# GUC_KATMANI.net
KiCad netlist of a schematic drawn in EAGLE
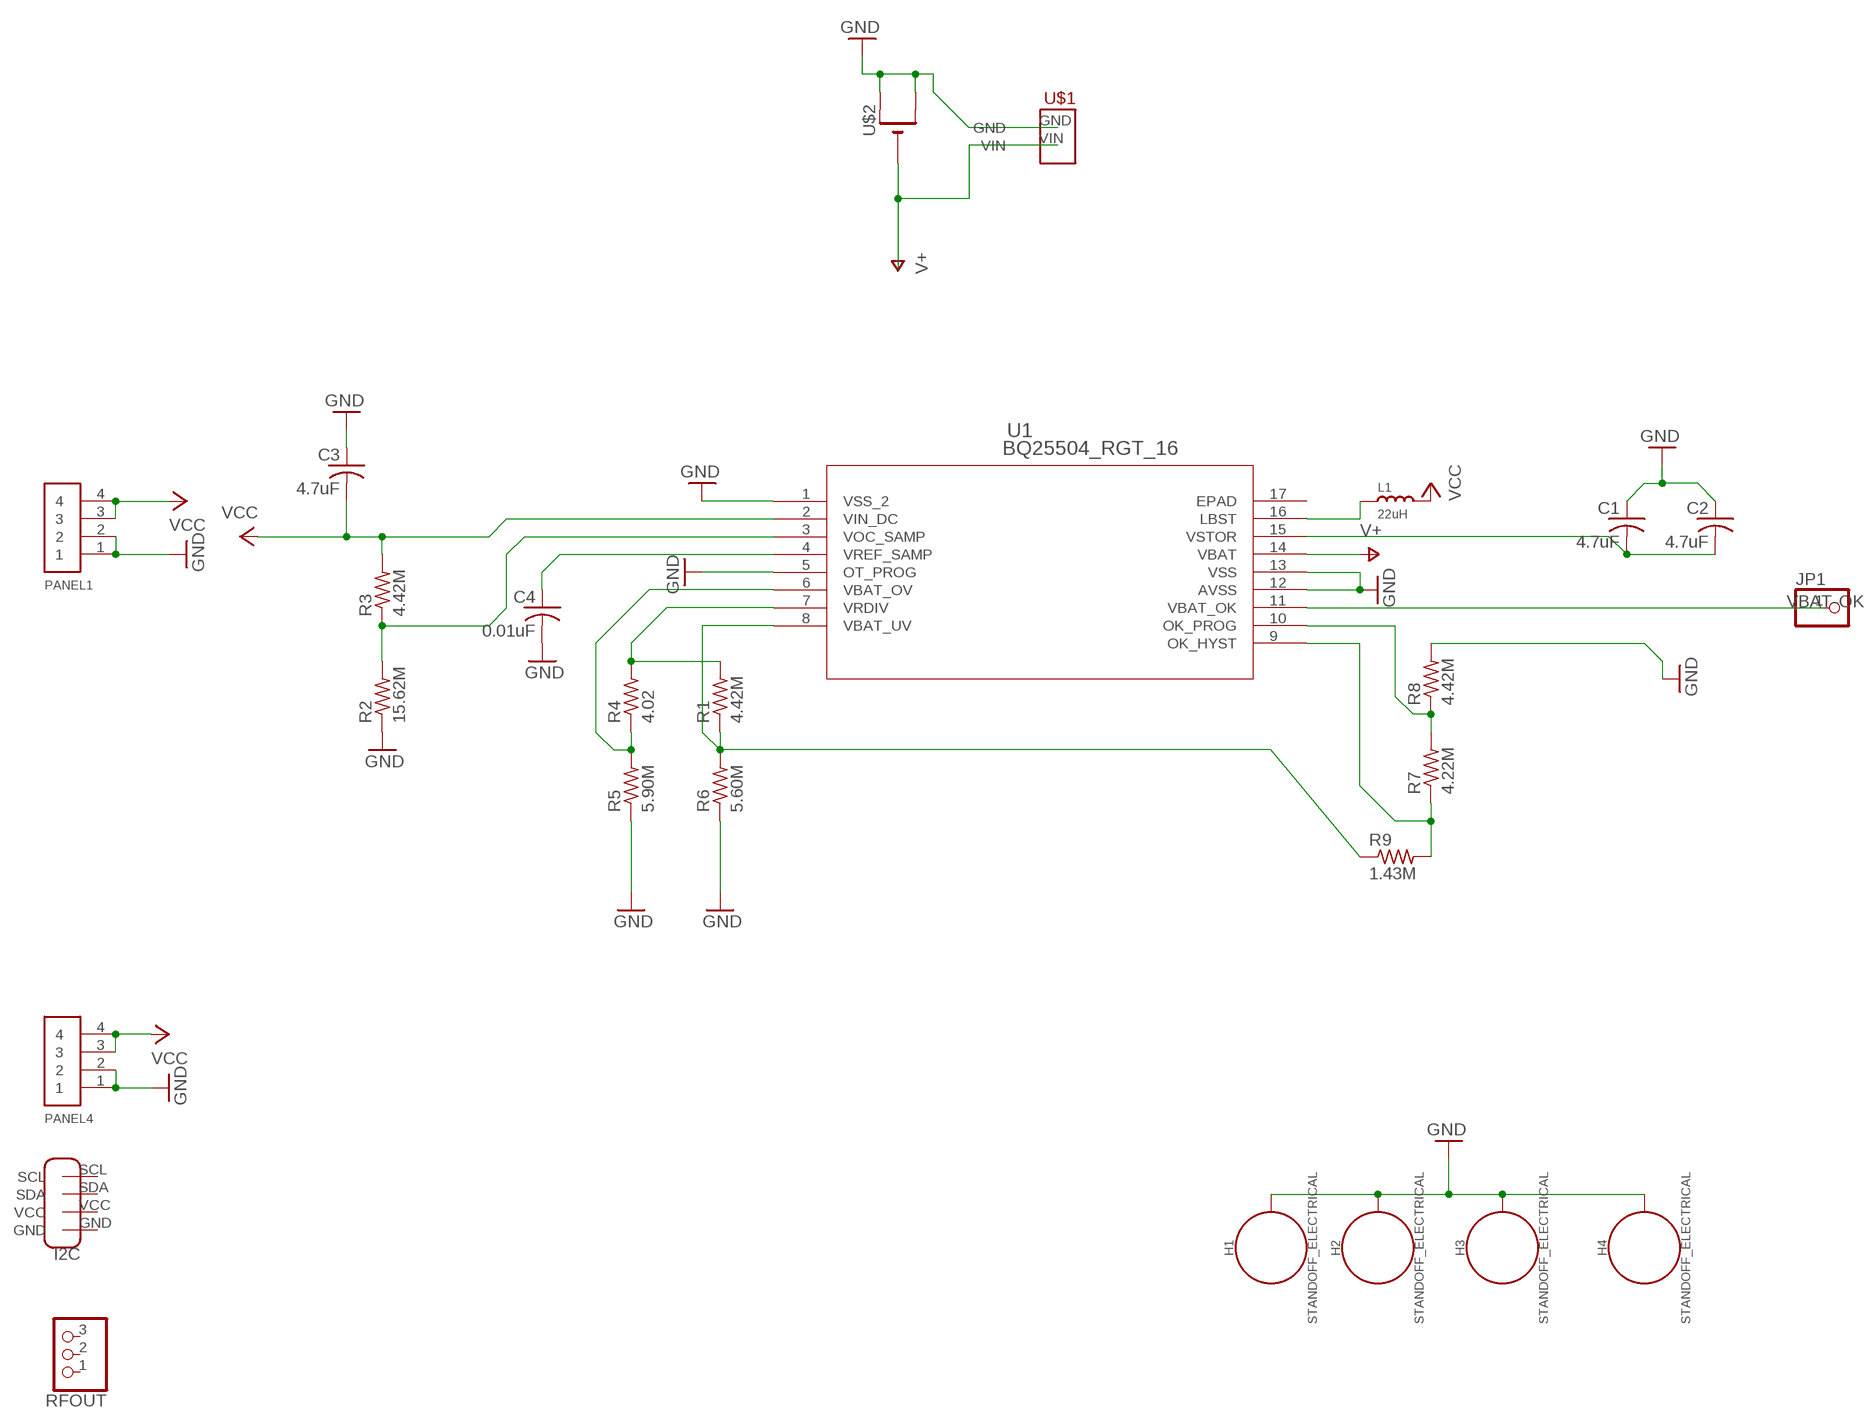
[diagram p0: schematic, sheet 1]

(export (version "E")
  (design (tool "Eeschema 10.0.6"))
  (components
    (comp (ref "C1")
      (value "4.7uF")
      (footprint "eagle-import:C0805K")
      (libsource (lib "eagle-import") (part "C-USC0805K"))
    )
    (comp (ref "C2")
      (value "4.7uF")
      (footprint "eagle-import:C0805K")
      (libsource (lib "eagle-import") (part "C-USC0805K"))
    )
    (comp (ref "C3")
      (value "4.7uF")
      (footprint "eagle-import:C0805K")
      (libsource (lib "eagle-import") (part "C-USC0805K"))
    )
    (comp (ref "C4")
      (value "0.01uF")
      (footprint "eagle-import:C0805K")
      (libsource (lib "eagle-import") (part "C-USC0805K"))
    )
    (comp (ref "H1")
      (value "STANDOFF_ELECTRICAL")
      (footprint "eagle-import:STANDOFF-ELECTRICAL")
      (libsource (lib "eagle-import") (part "STANDOFF_ELECTRICAL"))
    )
    (comp (ref "H2")
      (value "STANDOFF_ELECTRICAL")
      (footprint "eagle-import:STANDOFF-ELECTRICAL")
      (libsource (lib "eagle-import") (part "STANDOFF_ELECTRICAL"))
    )
    (comp (ref "H3")
      (value "STANDOFF_ELECTRICAL")
      (footprint "eagle-import:STANDOFF-ELECTRICAL")
      (libsource (lib "eagle-import") (part "STANDOFF_ELECTRICAL"))
    )
    (comp (ref "H4")
      (value "STANDOFF_ELECTRICAL")
      (footprint "eagle-import:STANDOFF-ELECTRICAL")
      (libsource (lib "eagle-import") (part "STANDOFF_ELECTRICAL"))
    )
    (comp (ref "JP1")
      (value "PINHD-1X1CB")
      (footprint "eagle-import:1X01-CLEANBIG")
      (libsource (lib "eagle-import") (part "PINHD-1X1CB"))
    )
    (comp (ref "L1")
      (value "22uH")
      (footprint "eagle-import:L0805")
      (fields (field (name "MPN") "BLM21PG331SN1D"))
      (libsource (lib "eagle-import") (part "SMD-FERRITE-BEAD-330R-1500MA(0805)'0805'"))
    )
    (comp (ref "PANEL1")
      (value "1X4-CLEANBIG")
      (footprint "eagle-import:1X04-CLEANBIG")
      (libsource (lib "eagle-import") (part "1X4-CLEANBIG"))
    )
    (comp (ref "PANEL4")
      (value "1X4-CLEANBIG")
      (footprint "eagle-import:1X04-CLEANBIG")
      (libsource (lib "eagle-import") (part "1X4-CLEANBIG"))
    )
    (comp (ref "R1")
      (value "4.42M")
      (footprint "eagle-import:R0805")
      (libsource (lib "eagle-import") (part "R-US_R0805"))
    )
    (comp (ref "R2")
      (value "15.62M")
      (footprint "eagle-import:R0805")
      (libsource (lib "eagle-import") (part "R-US_R0805"))
    )
    (comp (ref "R3")
      (value "4.42M")
      (footprint "eagle-import:R0805")
      (libsource (lib "eagle-import") (part "R-US_R0805"))
    )
    (comp (ref "R4")
      (value "4.02")
      (footprint "eagle-import:R0805")
      (libsource (lib "eagle-import") (part "R-US_R0805"))
    )
    (comp (ref "R5")
      (value "5.90M")
      (footprint "eagle-import:R0805")
      (libsource (lib "eagle-import") (part "R-US_R0805"))
    )
    (comp (ref "R6")
      (value "5.60M")
      (footprint "eagle-import:R0805")
      (libsource (lib "eagle-import") (part "R-US_R0805"))
    )
    (comp (ref "R7")
      (value "4.22M")
      (footprint "eagle-import:R0805")
      (libsource (lib "eagle-import") (part "R-US_R0805"))
    )
    (comp (ref "R8")
      (value "4.42M")
      (footprint "eagle-import:R0805")
      (libsource (lib "eagle-import") (part "R-US_R0805"))
    )
    (comp (ref "R9")
      (value "1.43M")
      (footprint "eagle-import:R0805")
      (libsource (lib "eagle-import") (part "R-US_R0805"))
    )
    (comp (ref "RFOUT")
      (value "PINHD-1X3CB")
      (footprint "eagle-import:1X03-CLEANBIG")
      (libsource (lib "eagle-import") (part "PINHD-1X3CB"))
    )
    (comp (ref "U$1")
      (value "2PINKLEMENS")
      (footprint "eagle-import:2PINKLEMENS")
      (libsource (lib "eagle-import") (part "2PINKLEMENS"))
    )
    (comp (ref "U$2")
      (value "CR1220SMT")
      (footprint "eagle-import:CR1220-SMD")
      (libsource (lib "eagle-import") (part "CR1220SMT"))
    )
    (comp (ref "U$3")
      (value "I2C")
      (footprint "eagle-import:I2C")
      (libsource (lib "eagle-import") (part "I2C"))
    )
    (comp (ref "U1")
      (value "BQ25504_RGT_16")
      (footprint "eagle-import:RGT16_1P7X1P7")
      (fields
        (field (name "GENERIC_PART_NUMBER") "BQ25504")
        (field (name "MANUFACTURER") "Texas Instruments")
      )
      (libsource (lib "eagle-import") (part "BQ25504_RGT_16"))
    )
  )
  (nets
    (net (code "1") (name "/EPAD") (class "Default")
      (node (ref "U1") (pin "17") (pinfunction "EPAD_17") (pintype "power_in"))
    )
    (net (code "2") (name "/VBAT-OK") (class "Default")
      (node (ref "JP1") (pin "1") (pinfunction "1_1") (pintype "passive"))
      (node (ref "U1") (pin "11") (pinfunction "VBAT_OK_11") (pintype "output"))
    )
    (net (code "3") (name "GND") (class "Default")
      (node (ref "C1") (pin "1") (pinfunction "1_1") (pintype "passive"))
      (node (ref "C2") (pin "1") (pinfunction "1_1") (pintype "passive"))
      (node (ref "C3") (pin "1") (pinfunction "1_1") (pintype "passive"))
      (node (ref "C4") (pin "2") (pinfunction "2_2") (pintype "passive"))
      (node (ref "H1") (pin "P1") (pinfunction "P$1_P1") (pintype "bidirectional"))
      (node (ref "H2") (pin "P1") (pinfunction "P$1_P1") (pintype "bidirectional"))
      (node (ref "H3") (pin "P1") (pinfunction "P$1_P1") (pintype "bidirectional"))
      (node (ref "H4") (pin "P1") (pinfunction "P$1_P1") (pintype "bidirectional"))
      (node (ref "PANEL1") (pin "1") (pinfunction "1_1") (pintype "bidirectional"))
      (node (ref "PANEL1") (pin "2") (pinfunction "2_2") (pintype "bidirectional"))
      (node (ref "PANEL4") (pin "1") (pinfunction "1_1") (pintype "bidirectional"))
      (node (ref "PANEL4") (pin "2") (pinfunction "2_2") (pintype "bidirectional"))
      (node (ref "R2") (pin "1") (pinfunction "1_1") (pintype "passive"))
      (node (ref "R5") (pin "1") (pinfunction "1_1") (pintype "passive"))
      (node (ref "R6") (pin "1") (pinfunction "1_1") (pintype "passive"))
      (node (ref "R8") (pin "2") (pinfunction "2_2") (pintype "passive"))
      (node (ref "U$1") (pin "GND") (pinfunction "GND_GND") (pintype "bidirectional"))
      (node (ref "U$2") (pin "+$1") (pinfunction "+_+$1") (pintype "passive"))
      (node (ref "U$2") (pin "+$2") (pinfunction "+1_+$2") (pintype "passive"))
      (node (ref "U1") (pin "1") (pinfunction "VSS_2_1") (pintype "power_in"))
      (node (ref "U1") (pin "12") (pinfunction "AVSS_12") (pintype "power_in"))
      (node (ref "U1") (pin "13") (pinfunction "VSS_13") (pintype "power_in"))
      (node (ref "U1") (pin "5") (pinfunction "OT_PROG_5") (pintype "input"))
    )
    (net (code "4") (name "Net-(U1-LBST)") (class "Default")
      (node (ref "L1") (pin "1") (pinfunction "1_1") (pintype "passive"))
      (node (ref "U1") (pin "16") (pinfunction "LBST_16") (pintype "input"))
    )
    (net (code "5") (name "Net-(U1-OK_HYST)") (class "Default")
      (node (ref "R7") (pin "1") (pinfunction "1_1") (pintype "passive"))
      (node (ref "R9") (pin "2") (pinfunction "2_2") (pintype "passive"))
      (node (ref "U1") (pin "9") (pinfunction "OK_HYST_9") (pintype "input"))
    )
    (net (code "6") (name "Net-(U1-OK_PROG)") (class "Default")
      (node (ref "R7") (pin "2") (pinfunction "2_2") (pintype "passive"))
      (node (ref "R8") (pin "1") (pinfunction "1_1") (pintype "passive"))
      (node (ref "U1") (pin "10") (pinfunction "OK_PROG_10") (pintype "input"))
    )
    (net (code "7") (name "Net-(U1-VBAT_OV)") (class "Default")
      (node (ref "R4") (pin "1") (pinfunction "1_1") (pintype "passive"))
      (node (ref "R5") (pin "2") (pinfunction "2_2") (pintype "passive"))
      (node (ref "U1") (pin "6") (pinfunction "VBAT_OV_6") (pintype "input"))
    )
    (net (code "8") (name "Net-(U1-VBAT_UV)") (class "Default")
      (node (ref "R1") (pin "1") (pinfunction "1_1") (pintype "passive"))
      (node (ref "R6") (pin "2") (pinfunction "2_2") (pintype "passive"))
      (node (ref "R9") (pin "1") (pinfunction "1_1") (pintype "passive"))
      (node (ref "U1") (pin "8") (pinfunction "VBAT_UV_8") (pintype "input"))
    )
    (net (code "9") (name "Net-(U1-VOC_SAMP)") (class "Default")
      (node (ref "R2") (pin "2") (pinfunction "2_2") (pintype "passive"))
      (node (ref "R3") (pin "1") (pinfunction "1_1") (pintype "passive"))
      (node (ref "U1") (pin "3") (pinfunction "VOC_SAMP_3") (pintype "input"))
    )
    (net (code "10") (name "Net-(U1-VRDIV)") (class "Default")
      (node (ref "R1") (pin "2") (pinfunction "2_2") (pintype "passive"))
      (node (ref "R4") (pin "2") (pinfunction "2_2") (pintype "passive"))
      (node (ref "U1") (pin "7") (pinfunction "VRDIV_7") (pintype "output"))
    )
    (net (code "11") (name "Net-(U1-VREF_SAMP)") (class "Default")
      (node (ref "C4") (pin "1") (pinfunction "1_1") (pintype "passive"))
      (node (ref "U1") (pin "4") (pinfunction "VREF_SAMP_4") (pintype "input"))
    )
    (net (code "12") (name "Net-(U1-VSTOR)") (class "Default")
      (node (ref "C1") (pin "2") (pinfunction "2_2") (pintype "passive"))
      (node (ref "C2") (pin "2") (pinfunction "2_2") (pintype "passive"))
      (node (ref "U1") (pin "15") (pinfunction "VSTOR_15") (pintype "output"))
    )
    (net (code "13") (name "V+") (class "Default")
      (node (ref "U$1") (pin "VIN") (pinfunction "VIN_VIN") (pintype "bidirectional"))
      (node (ref "U$2") (pin "-") (pinfunction "-_-") (pintype "passive"))
      (node (ref "U1") (pin "14") (pinfunction "VBAT_14") (pintype "bidirectional"))
    )
    (net (code "14") (name "VCC") (class "Default")
      (node (ref "C3") (pin "2") (pinfunction "2_2") (pintype "passive"))
      (node (ref "L1") (pin "2") (pinfunction "2_2") (pintype "passive"))
      (node (ref "PANEL1") (pin "3") (pinfunction "3_3") (pintype "bidirectional"))
      (node (ref "PANEL1") (pin "4") (pinfunction "4_4") (pintype "bidirectional"))
      (node (ref "PANEL4") (pin "3") (pinfunction "3_3") (pintype "bidirectional"))
      (node (ref "PANEL4") (pin "4") (pinfunction "4_4") (pintype "bidirectional"))
      (node (ref "R3") (pin "2") (pinfunction "2_2") (pintype "passive"))
      (node (ref "U1") (pin "2") (pinfunction "VIN_DC_2") (pintype "input"))
    )
    (net (code "15") (name "unconnected-(RFOUT-Pad1)") (class "Default")
      (node (ref "RFOUT") (pin "1") (pinfunction "1_1") (pintype "passive"))
    )
    (net (code "16") (name "unconnected-(RFOUT-Pad2)") (class "Default")
      (node (ref "RFOUT") (pin "2") (pinfunction "2_2") (pintype "passive"))
    )
    (net (code "17") (name "unconnected-(RFOUT-Pad3)") (class "Default")
      (node (ref "RFOUT") (pin "3") (pinfunction "3_3") (pintype "passive"))
    )
    (net (code "18") (name "unconnected-(U$3-PadGND)") (class "Default")
      (node (ref "U$3") (pin "GND") (pinfunction "GND_GND") (pintype "bidirectional"))
    )
    (net (code "19") (name "unconnected-(U$3-PadSCL)") (class "Default")
      (node (ref "U$3") (pin "SCL") (pinfunction "SCL_SCL") (pintype "bidirectional"))
    )
    (net (code "20") (name "unconnected-(U$3-PadSDA)") (class "Default")
      (node (ref "U$3") (pin "SDA") (pinfunction "SDA_SDA") (pintype "bidirectional"))
    )
    (net (code "21") (name "unconnected-(U$3-PadVCC)") (class "Default")
      (node (ref "U$3") (pin "VCC") (pinfunction "VCC_VCC") (pintype "bidirectional"))
    )
  )
)
